# PHOTO_COMMUNICATION.net
KiCad netlist of a schematic drawn in Altium Designer
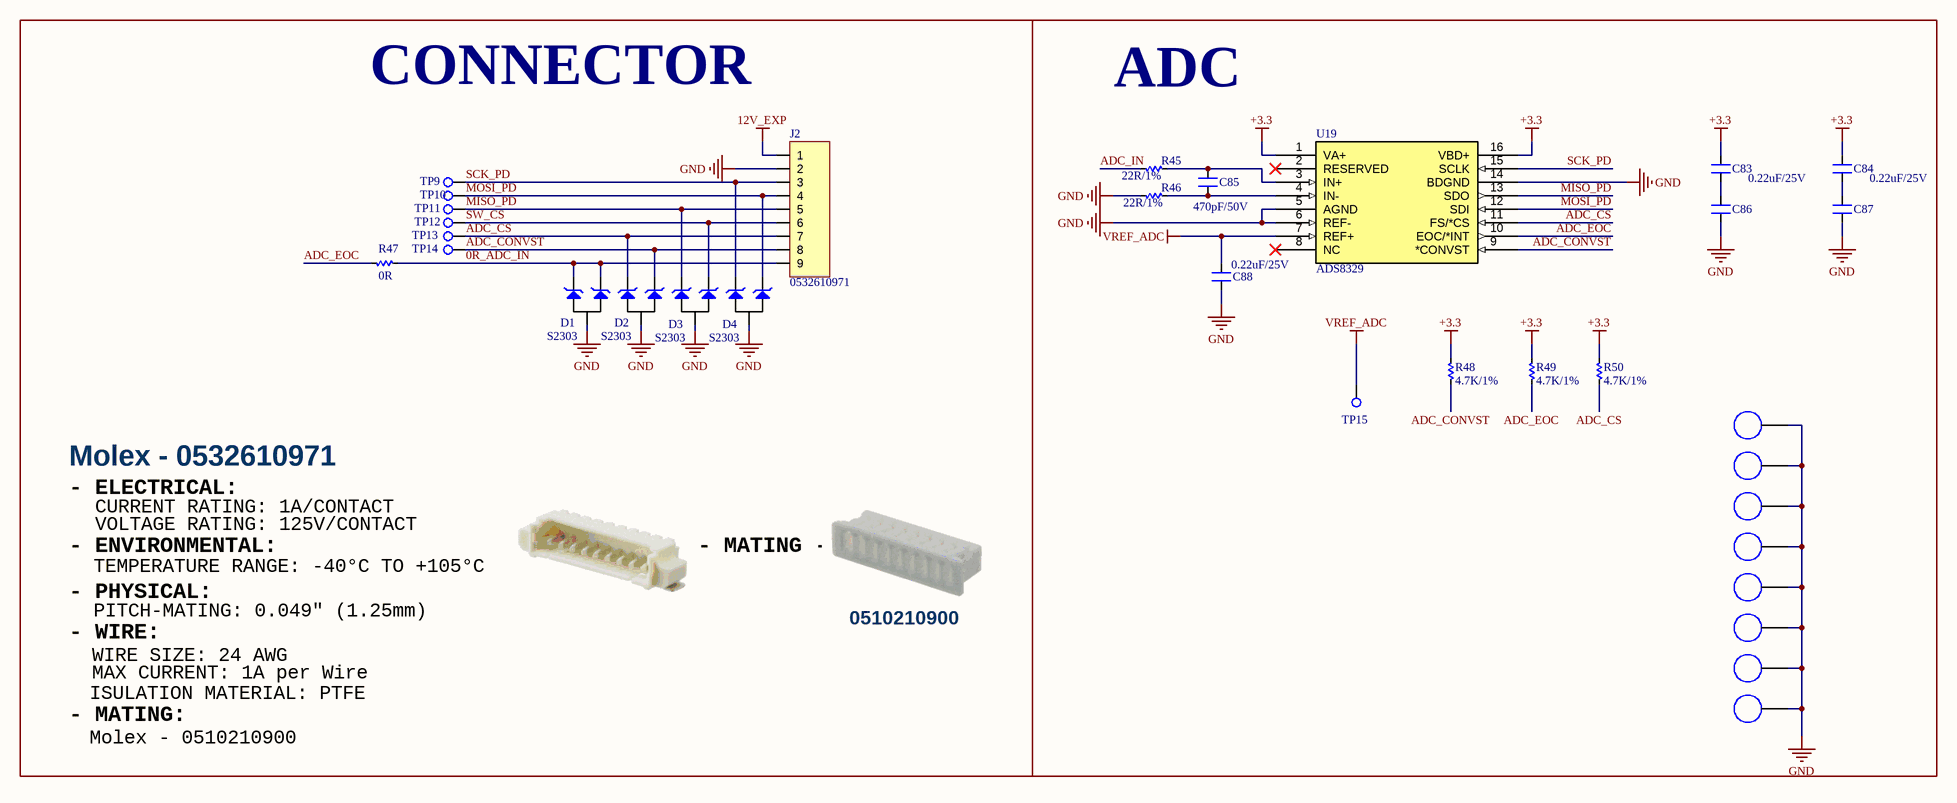
[diagram p0: PHOTO_COMMUNICATION.SchDoc]

(export (version "E")
  (design (tool "Eeschema 10.0.6"))
  (components
    (comp (ref "C83")
      (value "0.22uF/25V")
      (footprint "CN-SMD-0603")
      (description "CL10B224KA8NNNC")
      (libsource (lib "Capacitors") (part "CM"))
    )
    (comp (ref "C84")
      (value "0.22uF/25V")
      (footprint "CN-SMD-0603")
      (description "CL10B224KA8NNNC")
      (libsource (lib "Capacitors") (part "CM"))
    )
    (comp (ref "C85")
      (value "470pF/50V")
      (footprint "CN-SMD-0603")
      (description "CL10B471KB8NNNC")
      (libsource (lib "Capacitors") (part "CM"))
    )
    (comp (ref "C86")
      (value "0.22uF/25V")
      (footprint "CN-SMD-0603")
      (description "CL10B224KA8NNNC")
      (libsource (lib "Capacitors") (part "CM"))
    )
    (comp (ref "C87")
      (value "0.22uF/25V")
      (footprint "CN-SMD-0603")
      (description "CL10B224KA8NNNC")
      (libsource (lib "Capacitors") (part "CM"))
    )
    (comp (ref "C88")
      (value "0.22uF/25V")
      (footprint "CN-SMD-0603")
      (description "CL10B224KA8NNNC")
      (libsource (lib "Capacitors") (part "CM"))
    )
    (comp (ref "D1") (value "S2303") (footprint "SOT23-123") (libsource (lib "Library") (part "S2303")))
    (comp (ref "D2") (value "S2303") (footprint "SOT23-123") (libsource (lib "Library") (part "S2303")))
    (comp (ref "D3") (value "S2303") (footprint "SOT23-123") (libsource (lib "Library") (part "S2303")))
    (comp (ref "D4") (value "S2303") (footprint "SOT23-123") (libsource (lib "Library") (part "S2303")))
    (comp (ref "H5")
      (value "HOLD")
      (footprint "HEX-M3_NoVia_Smaller")
      (libsource (lib "Library_HUNG") (part "PAD_HOLD"))
    )
    (comp (ref "H6")
      (value "HOLD")
      (footprint "HEX-M3_NoVia_Smaller")
      (libsource (lib "Library_HUNG") (part "PAD_HOLD"))
    )
    (comp (ref "H7")
      (value "HOLD")
      (footprint "HEX-M3_NoVia_Smaller")
      (libsource (lib "Library_HUNG") (part "PAD_HOLD"))
    )
    (comp (ref "H8")
      (value "HOLD")
      (footprint "HEX-M3_NoVia_Smaller")
      (libsource (lib "Library_HUNG") (part "PAD_HOLD"))
    )
    (comp (ref "H9")
      (value "HOLD")
      (footprint "HEX-M3_NoVia_Smaller")
      (libsource (lib "Library_HUNG") (part "PAD_HOLD"))
    )
    (comp (ref "H10")
      (value "HOLD")
      (footprint "HEX-M3_NoVia_Smaller")
      (libsource (lib "Library_HUNG") (part "PAD_HOLD"))
    )
    (comp (ref "H11")
      (value "HOLD")
      (footprint "HEX-M3_NoVia_Smaller")
      (libsource (lib "Library_HUNG") (part "PAD_HOLD"))
    )
    (comp (ref "H12")
      (value "HOLD")
      (footprint "HEX-M3_NoVia_Smaller")
      (libsource (lib "Library_HUNG") (part "PAD_HOLD"))
    )
    (comp (ref "J2")
      (value "0532610971")
      (footprint "0532610971")
      (fields
        (field (name "MANUFACTURER") "Würth Elektronik eiSos GmbH")
        (field (name "PARTNO") "613009143121")
        (field (name "CREATED BY") "Karrer Zheng")
      )
      (libsource (lib "Library") (part "JP9"))
    )
    (comp (ref "R45")
      (value "22R/1%")
      (footprint "RES-SMD-0603")
      (description "ERJ-3EKF22R0V")
      (fields
        (field (name "MANUFACTURER") "Generic Components")
        (field (name "PUBLISHER") "Altium Hobart Technology Centre")
      )
      (libsource (lib "Library") (part "Res-SMD"))
    )
    (comp (ref "R46")
      (value "22R/1%")
      (footprint "RES-SMD-0603")
      (description "ERJ-3EKF22R0V")
      (fields
        (field (name "MANUFACTURER") "Generic Components")
        (field (name "PUBLISHER") "Altium Hobart Technology Centre")
      )
      (libsource (lib "Library") (part "Res-SMD"))
    )
    (comp (ref "R47")
      (value "0R")
      (footprint "RES-SMD-0603")
      (description "ERJ-3GEY0R00V")
      (fields
        (field (name "MANUFACTURER") "Generic Components")
        (field (name "PUBLISHER") "Altium Hobart Technology Centre")
      )
      (libsource (lib "Library") (part "Res-SMD"))
    )
    (comp (ref "R48")
      (value "4.7K/1%")
      (footprint "RES-SMD-0603")
      (description "ERJ-3EKF4701V")
      (fields
        (field (name "MANUFACTURER") "Generic Components")
        (field (name "PUBLISHER") "Altium Hobart Technology Centre")
      )
      (libsource (lib "Library") (part "Res-SMD"))
    )
    (comp (ref "R49")
      (value "4.7K/1%")
      (footprint "RES-SMD-0603")
      (description "ERJ-3EKF4701V")
      (fields
        (field (name "MANUFACTURER") "Generic Components")
        (field (name "PUBLISHER") "Altium Hobart Technology Centre")
      )
      (libsource (lib "Library") (part "Res-SMD"))
    )
    (comp (ref "R50")
      (value "4.7K/1%")
      (footprint "RES-SMD-0603")
      (description "ERJ-3EKF4701V")
      (fields
        (field (name "MANUFACTURER") "Generic Components")
        (field (name "PUBLISHER") "Altium Hobart Technology Centre")
      )
      (libsource (lib "Library") (part "Res-SMD"))
    )
    (comp (ref "TP9")
      (value "Test_Point")
      (footprint "TESTPOINT")
      (libsource (lib "Library_HUNG") (part "Test_Point"))
    )
    (comp (ref "TP10")
      (value "Test_Point")
      (footprint "TESTPOINT")
      (libsource (lib "Library_HUNG") (part "Test_Point"))
    )
    (comp (ref "TP11")
      (value "Test_Point")
      (footprint "TESTPOINT")
      (libsource (lib "Library_HUNG") (part "Test_Point"))
    )
    (comp (ref "TP12")
      (value "Test_Point")
      (footprint "TESTPOINT")
      (libsource (lib "Library_HUNG") (part "Test_Point"))
    )
    (comp (ref "TP13")
      (value "Test_Point")
      (footprint "TESTPOINT")
      (libsource (lib "Library_HUNG") (part "Test_Point"))
    )
    (comp (ref "TP14")
      (value "Test_Point")
      (footprint "TESTPOINT")
      (libsource (lib "Library_HUNG") (part "Test_Point"))
    )
    (comp (ref "TP15")
      (value "Test_Point")
      (footprint "TESTPOINT")
      (libsource (lib "Library_HUNG") (part "Test_Point"))
    )
    (comp (ref "U19") (value "ADS8329") (footprint "TSSOP16") (libsource (lib "Library") (part "ADS8327")))
  )
  (nets
    (net (code "1") (name "+3.3") (class "Default")
      (node (ref "C83") (pin "2") (pinfunction "2_2") (pintype "passive"))
      (node (ref "C84") (pin "2") (pinfunction "2_2") (pintype "passive"))
      (node (ref "R48") (pin "2") (pinfunction "2_2") (pintype "passive"))
      (node (ref "R49") (pin "2") (pinfunction "2_2") (pintype "passive"))
      (node (ref "R50") (pin "2") (pinfunction "2_2") (pintype "passive"))
      (node (ref "U19") (pin "1") (pinfunction "VA+_1") (pintype "power_in"))
      (node (ref "U19") (pin "16") (pinfunction "VBD+_16") (pintype "power_in"))
    )
    (net (code "2") (name "/0R_ADC_IN") (class "Default")
      (node (ref "D1") (pin "1") (pintype "passive"))
      (node (ref "D1") (pin "3") (pintype "passive"))
      (node (ref "J2") (pin "9") (pinfunction "9_9") (pintype "passive"))
      (node (ref "R47") (pin "1") (pinfunction "1_1") (pintype "passive"))
    )
    (net (code "3") (name "/ADC_CONVST") (class "Default")
      (node (ref "D2") (pin "3") (pintype "passive"))
      (node (ref "J2") (pin "8") (pinfunction "8_8") (pintype "passive"))
      (node (ref "R48") (pin "1") (pinfunction "1_1") (pintype "passive"))
      (node (ref "TP14") (pin "1") (pintype "power_in"))
      (node (ref "U19") (pin "9") (pinfunction "*CONVST_9") (pintype "input"))
    )
    (net (code "4") (name "/ADC_CS") (class "Default")
      (node (ref "D2") (pin "1") (pintype "passive"))
      (node (ref "J2") (pin "7") (pinfunction "7_7") (pintype "passive"))
      (node (ref "R50") (pin "1") (pinfunction "1_1") (pintype "passive"))
      (node (ref "TP13") (pin "1") (pintype "power_in"))
      (node (ref "U19") (pin "11") (pinfunction "FS/*CS_11") (pintype "input"))
    )
    (net (code "5") (name "/ADC_EOC") (class "Default")
      (node (ref "R47") (pin "2") (pinfunction "2_2") (pintype "passive"))
      (node (ref "R49") (pin "1") (pinfunction "1_1") (pintype "passive"))
      (node (ref "U19") (pin "10") (pinfunction "EOC/*INT_10") (pintype "output"))
    )
    (net (code "6") (name "/ADC_IN") (class "Default")
      (node (ref "R45") (pin "2") (pinfunction "2_2") (pintype "passive"))
    )
    (net (code "7") (name "/MISO_PD") (class "Default")
      (node (ref "D3") (pin "1") (pintype "passive"))
      (node (ref "J2") (pin "5") (pinfunction "5_5") (pintype "passive"))
      (node (ref "TP11") (pin "1") (pintype "power_in"))
      (node (ref "U19") (pin "13") (pinfunction "SDO_13") (pintype "output"))
    )
    (net (code "8") (name "/MOSI_PD") (class "Default")
      (node (ref "D4") (pin "3") (pintype "passive"))
      (node (ref "J2") (pin "4") (pinfunction "4_4") (pintype "passive"))
      (node (ref "TP10") (pin "1") (pintype "power_in"))
      (node (ref "U19") (pin "12") (pinfunction "SDI_12") (pintype "input"))
    )
    (net (code "9") (name "/SCK_PD") (class "Default")
      (node (ref "D4") (pin "1") (pintype "passive"))
      (node (ref "J2") (pin "3") (pinfunction "3_3") (pintype "passive"))
      (node (ref "TP9") (pin "1") (pintype "power_in"))
      (node (ref "U19") (pin "15") (pinfunction "SCLK_15") (pintype "input"))
    )
    (net (code "10") (name "/SW_CS") (class "Default")
      (node (ref "D3") (pin "3") (pintype "passive"))
      (node (ref "J2") (pin "6") (pinfunction "6_6") (pintype "passive"))
      (node (ref "TP12") (pin "1") (pintype "power_in"))
    )
    (net (code "11") (name "12V_EXP") (class "Default")
      (node (ref "J2") (pin "1") (pinfunction "1_1") (pintype "passive"))
    )
    (net (code "12") (name "GND") (class "Default")
      (node (ref "C86") (pin "1") (pinfunction "1_1") (pintype "passive"))
      (node (ref "C87") (pin "1") (pinfunction "1_1") (pintype "passive"))
      (node (ref "C88") (pin "1") (pinfunction "1_1") (pintype "passive"))
      (node (ref "D1") (pin "2") (pintype "passive"))
      (node (ref "D2") (pin "2") (pintype "passive"))
      (node (ref "D3") (pin "2") (pintype "passive"))
      (node (ref "D4") (pin "2") (pintype "passive"))
      (node (ref "H10") (pin "1") (pintype "power_in"))
      (node (ref "H11") (pin "1") (pintype "power_in"))
      (node (ref "H12") (pin "1") (pintype "power_in"))
      (node (ref "H5") (pin "1") (pintype "power_in"))
      (node (ref "H6") (pin "1") (pintype "power_in"))
      (node (ref "H7") (pin "1") (pintype "power_in"))
      (node (ref "H8") (pin "1") (pintype "power_in"))
      (node (ref "H9") (pin "1") (pintype "power_in"))
      (node (ref "J2") (pin "2") (pinfunction "2_2") (pintype "passive"))
      (node (ref "R46") (pin "2") (pinfunction "2_2") (pintype "passive"))
      (node (ref "U19") (pin "14") (pinfunction "BDGND_14") (pintype "power_in"))
      (node (ref "U19") (pin "5") (pinfunction "AGND_5") (pintype "power_in"))
      (node (ref "U19") (pin "6") (pinfunction "REF-_6") (pintype "input"))
    )
    (net (code "13") (name "Net-(C83-Pad1)") (class "Default")
      (node (ref "C83") (pin "1") (pinfunction "1_1") (pintype "passive"))
      (node (ref "C86") (pin "2") (pinfunction "2_2") (pintype "passive"))
    )
    (net (code "14") (name "Net-(C84-Pad1)") (class "Default")
      (node (ref "C84") (pin "1") (pinfunction "1_1") (pintype "passive"))
      (node (ref "C87") (pin "2") (pinfunction "2_2") (pintype "passive"))
    )
    (net (code "15") (name "Net-(U19-IN+)") (class "Default")
      (node (ref "C85") (pin "2") (pinfunction "2_2") (pintype "passive"))
      (node (ref "R45") (pin "1") (pinfunction "1_1") (pintype "passive"))
      (node (ref "U19") (pin "3") (pinfunction "IN+_3") (pintype "input"))
    )
    (net (code "16") (name "Net-(U19-IN-)") (class "Default")
      (node (ref "C85") (pin "1") (pinfunction "1_1") (pintype "passive"))
      (node (ref "R46") (pin "1") (pinfunction "1_1") (pintype "passive"))
      (node (ref "U19") (pin "4") (pinfunction "IN-_4") (pintype "input"))
    )
    (net (code "17") (name "VREF_ADC") (class "Default")
      (node (ref "C88") (pin "2") (pinfunction "2_2") (pintype "passive"))
      (node (ref "TP15") (pin "1") (pintype "power_in"))
      (node (ref "U19") (pin "7") (pinfunction "REF+_7") (pintype "input"))
    )
    (net (code "18") (name "unconnected-(U19-NC-Pad8)") (class "Default")
      (node (ref "U19") (pin "8") (pinfunction "NC_8") (pintype "passive+no_connect"))
    )
    (net (code "19") (name "unconnected-(U19-RESERVED-Pad2)") (class "Default")
      (node (ref "U19") (pin "2") (pinfunction "RESERVED_2") (pintype "passive+no_connect"))
    )
  )
)
